# Bridge.net
KiCad netlist of a schematic drawn in Altium Designer
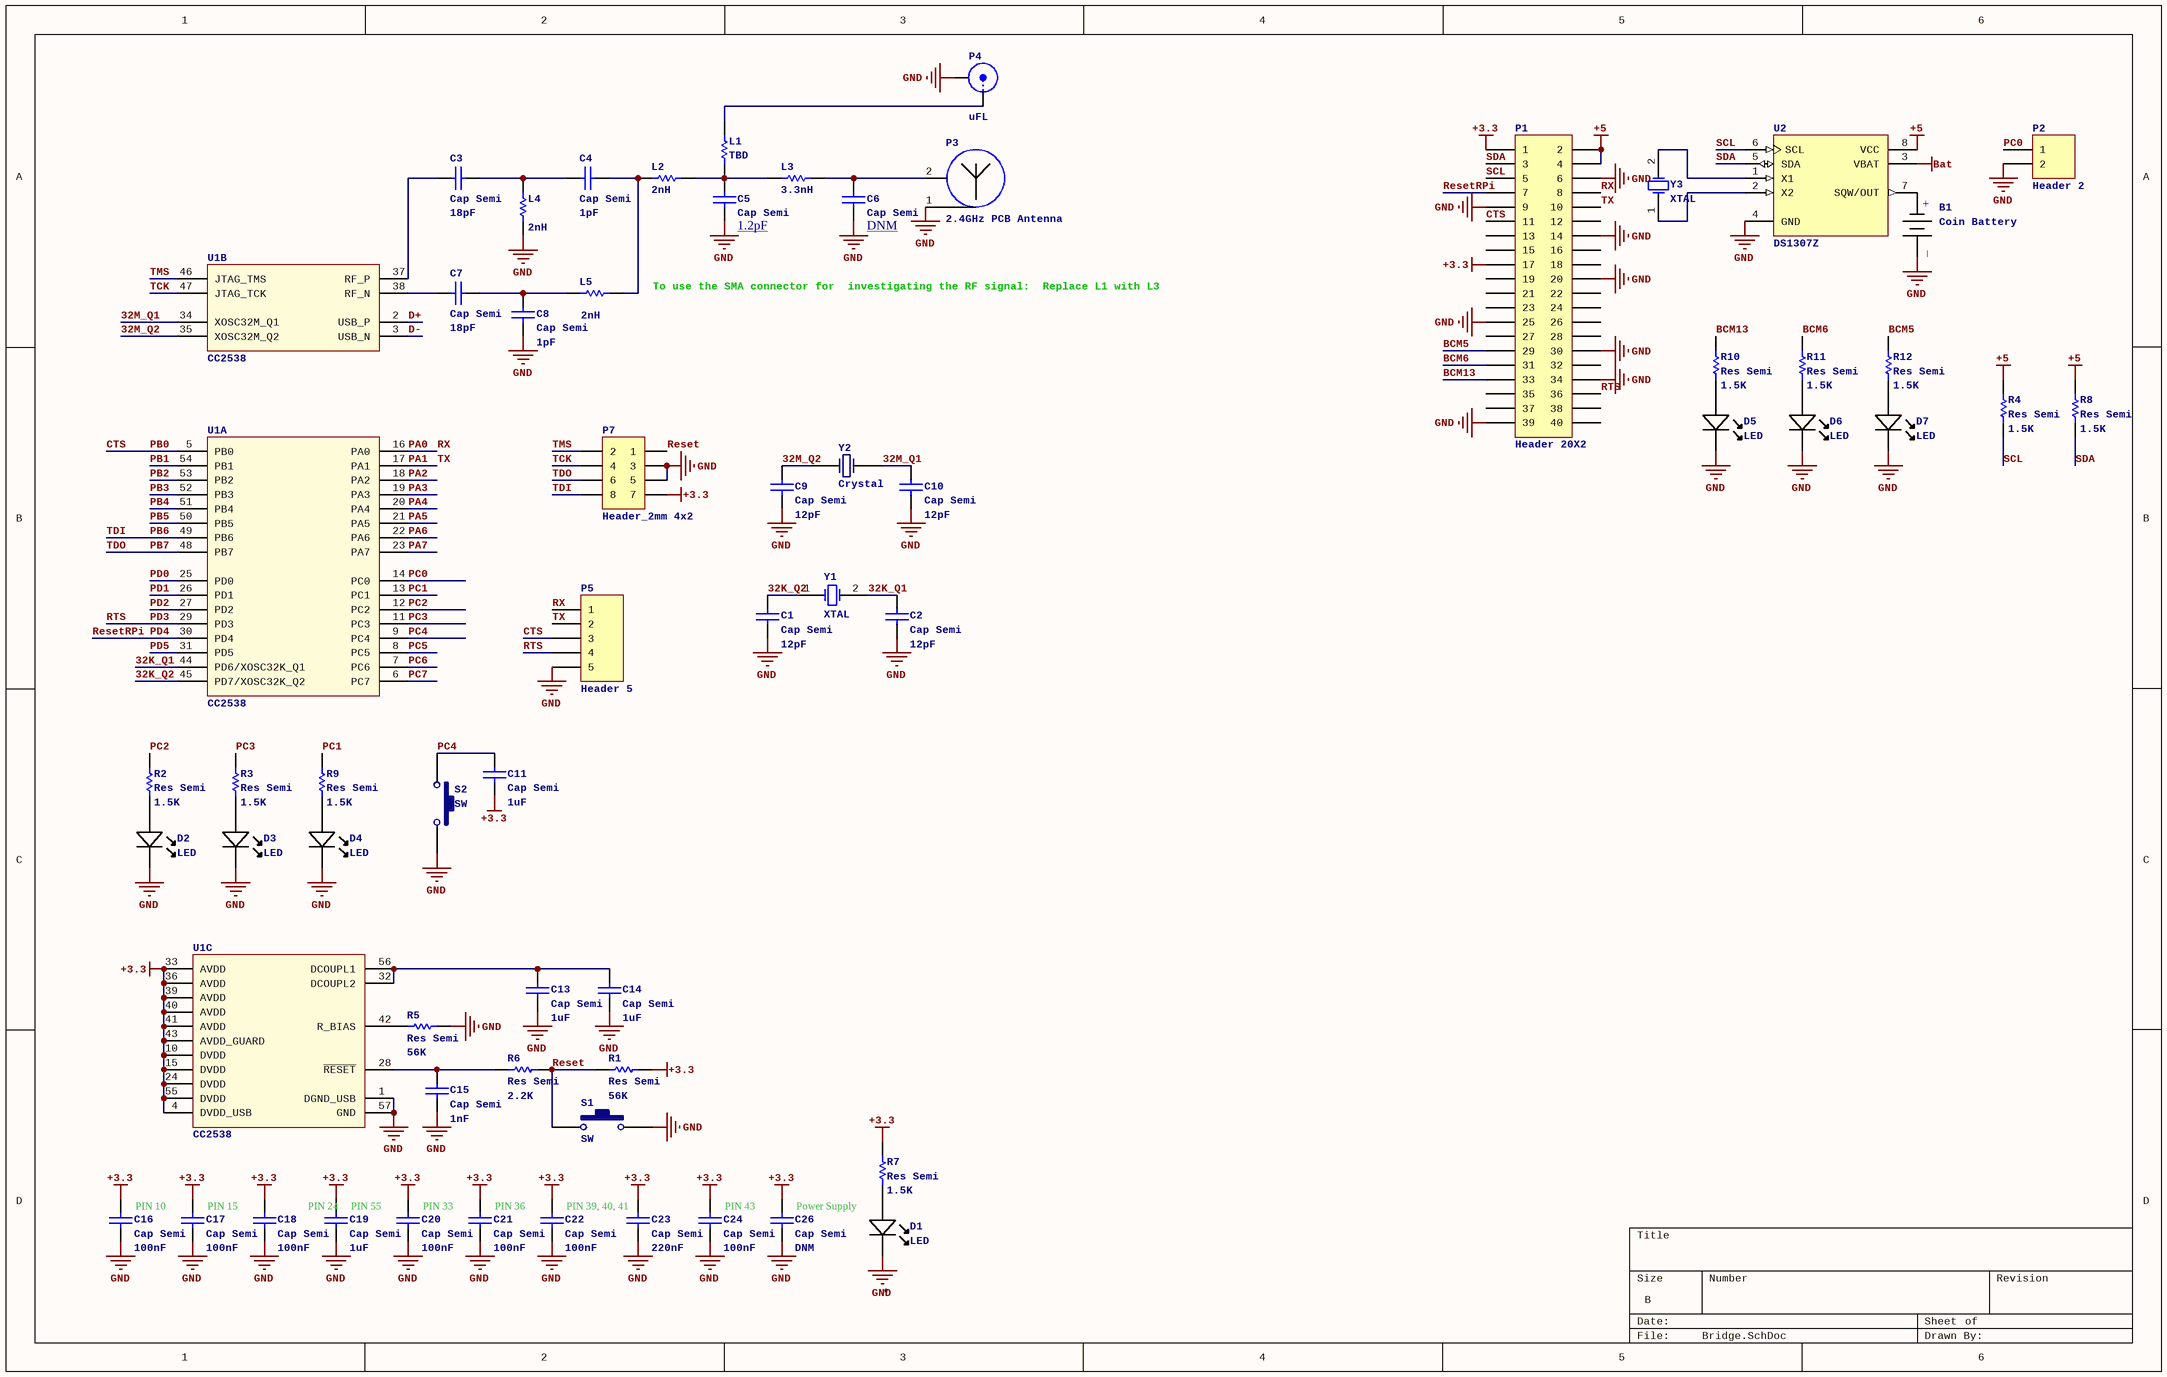
[diagram p0: Bridge.SchDoc]

(export (version "E")
  (design (tool "Eeschema 10.0.6"))
  (components
    (comp (ref "B1")
      (value "Coin Battery")
      (footprint "Coin Battery 1220")
      (libsource (lib "My Lib") (part "Coin Battery"))
    )
    (comp (ref "C1")
      (value "Cap Semi")
      (footprint "1608[0603]")
      (description "Capacitor (Semiconductor SIM Model)")
      (fields (field (name "ALTIUM_VALUE") "12pF") (field (name "PUBLISHER") "Altium Limited"))
      (libsource (lib "Miscellaneous Devices") (part "Cap Semi"))
    )
    (comp (ref "C2")
      (value "Cap Semi")
      (footprint "1608[0603]")
      (description "Capacitor (Semiconductor SIM Model)")
      (fields (field (name "ALTIUM_VALUE") "12pF") (field (name "PUBLISHER") "Altium Limited"))
      (libsource (lib "Miscellaneous Devices") (part "Cap Semi"))
    )
    (comp (ref "C3")
      (value "Cap Semi")
      (footprint "1608[0603]")
      (description "Capacitor (Semiconductor SIM Model)")
      (fields (field (name "ALTIUM_VALUE") "18pF") (field (name "PUBLISHER") "Altium Limited"))
      (libsource (lib "Miscellaneous Devices") (part "Cap Semi"))
    )
    (comp (ref "C4")
      (value "Cap Semi")
      (footprint "1608[0603]")
      (description "Capacitor (Semiconductor SIM Model)")
      (fields (field (name "ALTIUM_VALUE") "1pF") (field (name "PUBLISHER") "Altium Limited"))
      (libsource (lib "Miscellaneous Devices") (part "Cap Semi"))
    )
    (comp (ref "C5")
      (value "Cap Semi")
      (footprint "1608[0603]")
      (description "Capacitor (Semiconductor SIM Model)")
      (fields (field (name "ALTIUM_VALUE") "1.2pF") (field (name "PUBLISHER") "Altium Limited"))
      (libsource (lib "Miscellaneous Devices") (part "Cap Semi"))
    )
    (comp (ref "C6")
      (value "Cap Semi")
      (footprint "1608[0603]")
      (description "Capacitor (Semiconductor SIM Model)")
      (fields (field (name "ALTIUM_VALUE") "DNM") (field (name "PUBLISHER") "Altium Limited"))
      (libsource (lib "Miscellaneous Devices") (part "Cap Semi"))
    )
    (comp (ref "C7")
      (value "Cap Semi")
      (footprint "1608[0603]")
      (description "Capacitor (Semiconductor SIM Model)")
      (fields (field (name "ALTIUM_VALUE") "18pF") (field (name "PUBLISHER") "Altium Limited"))
      (libsource (lib "Miscellaneous Devices") (part "Cap Semi"))
    )
    (comp (ref "C8")
      (value "Cap Semi")
      (footprint "1608[0603]")
      (description "Capacitor (Semiconductor SIM Model)")
      (fields (field (name "ALTIUM_VALUE") "1pF") (field (name "PUBLISHER") "Altium Limited"))
      (libsource (lib "Miscellaneous Devices") (part "Cap Semi"))
    )
    (comp (ref "C9")
      (value "Cap Semi")
      (footprint "1608[0603]")
      (description "Capacitor (Semiconductor SIM Model)")
      (fields (field (name "ALTIUM_VALUE") "12pF") (field (name "PUBLISHER") "Altium Limited"))
      (libsource (lib "Miscellaneous Devices") (part "Cap Semi"))
    )
    (comp (ref "C10")
      (value "Cap Semi")
      (footprint "1608[0603]")
      (description "Capacitor (Semiconductor SIM Model)")
      (fields (field (name "ALTIUM_VALUE") "12pF") (field (name "PUBLISHER") "Altium Limited"))
      (libsource (lib "Miscellaneous Devices") (part "Cap Semi"))
    )
    (comp (ref "C11")
      (value "Cap Semi")
      (footprint "1608[0603]")
      (description "Capacitor (Semiconductor SIM Model)")
      (fields (field (name "ALTIUM_VALUE") "1uF") (field (name "PUBLISHER") "Altium Limited"))
      (libsource (lib "Miscellaneous Devices") (part "Cap Semi"))
    )
    (comp (ref "C13")
      (value "Cap Semi")
      (footprint "1608[0603]")
      (description "Capacitor (Semiconductor SIM Model)")
      (fields (field (name "ALTIUM_VALUE") "1uF") (field (name "PUBLISHER") "Altium Limited"))
      (libsource (lib "Miscellaneous Devices") (part "Cap Semi"))
    )
    (comp (ref "C14")
      (value "Cap Semi")
      (footprint "1608[0603]")
      (description "Capacitor (Semiconductor SIM Model)")
      (fields (field (name "ALTIUM_VALUE") "1uF") (field (name "PUBLISHER") "Altium Limited"))
      (libsource (lib "Miscellaneous Devices") (part "Cap Semi"))
    )
    (comp (ref "C15")
      (value "Cap Semi")
      (footprint "1608[0603]")
      (description "Capacitor (Semiconductor SIM Model)")
      (fields (field (name "ALTIUM_VALUE") "1nF") (field (name "PUBLISHER") "Altium Limited"))
      (libsource (lib "Miscellaneous Devices") (part "Cap Semi"))
    )
    (comp (ref "C16")
      (value "Cap Semi")
      (footprint "1608[0603]")
      (description "Capacitor (Semiconductor SIM Model)")
      (fields (field (name "ALTIUM_VALUE") "100nF") (field (name "PUBLISHER") "Altium Limited"))
      (libsource (lib "Miscellaneous Devices") (part "Cap Semi"))
    )
    (comp (ref "C17")
      (value "Cap Semi")
      (footprint "1608[0603]")
      (description "Capacitor (Semiconductor SIM Model)")
      (fields (field (name "ALTIUM_VALUE") "100nF") (field (name "PUBLISHER") "Altium Limited"))
      (libsource (lib "Miscellaneous Devices") (part "Cap Semi"))
    )
    (comp (ref "C18")
      (value "Cap Semi")
      (footprint "1608[0603]")
      (description "Capacitor (Semiconductor SIM Model)")
      (fields (field (name "ALTIUM_VALUE") "100nF") (field (name "PUBLISHER") "Altium Limited"))
      (libsource (lib "Miscellaneous Devices") (part "Cap Semi"))
    )
    (comp (ref "C19")
      (value "Cap Semi")
      (footprint "1608[0603]")
      (description "Capacitor (Semiconductor SIM Model)")
      (fields (field (name "ALTIUM_VALUE") "1uF") (field (name "PUBLISHER") "Altium Limited"))
      (libsource (lib "Miscellaneous Devices") (part "Cap Semi"))
    )
    (comp (ref "C20")
      (value "Cap Semi")
      (footprint "1608[0603]")
      (description "Capacitor (Semiconductor SIM Model)")
      (fields (field (name "ALTIUM_VALUE") "100nF") (field (name "PUBLISHER") "Altium Limited"))
      (libsource (lib "Miscellaneous Devices") (part "Cap Semi"))
    )
    (comp (ref "C21")
      (value "Cap Semi")
      (footprint "1608[0603]")
      (description "Capacitor (Semiconductor SIM Model)")
      (fields (field (name "ALTIUM_VALUE") "100nF") (field (name "PUBLISHER") "Altium Limited"))
      (libsource (lib "Miscellaneous Devices") (part "Cap Semi"))
    )
    (comp (ref "C22")
      (value "Cap Semi")
      (footprint "1608[0603]")
      (description "Capacitor (Semiconductor SIM Model)")
      (fields (field (name "ALTIUM_VALUE") "100nF") (field (name "PUBLISHER") "Altium Limited"))
      (libsource (lib "Miscellaneous Devices") (part "Cap Semi"))
    )
    (comp (ref "C23")
      (value "Cap Semi")
      (footprint "1608[0603]")
      (description "Capacitor (Semiconductor SIM Model)")
      (fields (field (name "ALTIUM_VALUE") "220nF") (field (name "PUBLISHER") "Altium Limited"))
      (libsource (lib "Miscellaneous Devices") (part "Cap Semi"))
    )
    (comp (ref "C24")
      (value "Cap Semi")
      (footprint "1608[0603]")
      (description "Capacitor (Semiconductor SIM Model)")
      (fields (field (name "ALTIUM_VALUE") "100nF") (field (name "PUBLISHER") "Altium Limited"))
      (libsource (lib "Miscellaneous Devices") (part "Cap Semi"))
    )
    (comp (ref "C26")
      (value "Cap Semi")
      (footprint "1608[0603]")
      (description "Capacitor (Semiconductor SIM Model)")
      (fields (field (name "ALTIUM_VALUE") "DNM") (field (name "PUBLISHER") "Altium Limited"))
      (libsource (lib "Miscellaneous Devices") (part "Cap Semi"))
    )
    (comp (ref "D1")
      (value "LED")
      (footprint "LED 0603")
      (description "LED SMD")
      (libsource (lib "Common") (part "LED SMD"))
    )
    (comp (ref "D2")
      (value "LED")
      (footprint "LED 0603")
      (description "LED SMD")
      (libsource (lib "Common") (part "LED SMD"))
    )
    (comp (ref "D3")
      (value "LED")
      (footprint "LED 0603")
      (description "LED SMD")
      (libsource (lib "Common") (part "LED SMD"))
    )
    (comp (ref "D4")
      (value "LED")
      (footprint "LED 0603")
      (description "LED SMD")
      (libsource (lib "Common") (part "LED SMD"))
    )
    (comp (ref "D5")
      (value "LED")
      (footprint "LED 0603")
      (description "LED SMD")
      (libsource (lib "Common") (part "LED SMD"))
    )
    (comp (ref "D6")
      (value "LED")
      (footprint "LED 0603")
      (description "LED SMD")
      (libsource (lib "Common") (part "LED SMD"))
    )
    (comp (ref "D7")
      (value "LED")
      (footprint "LED 0603")
      (description "LED SMD")
      (libsource (lib "Common") (part "LED SMD"))
    )
    (comp (ref "L1")
      (value "TBD")
      (footprint "1608[0603]")
      (description "Semiconductor Resistor")
      (fields (field (name "Comment") "Res Semi") (field (name "PUBLISHER") "Altium Limited"))
      (libsource (lib "Miscellaneous Devices") (part "Res Semi"))
    )
    (comp (ref "L2")
      (value "2nH")
      (footprint "1608[0603]")
      (description "Semiconductor Resistor")
      (fields (field (name "Comment") "Res Semi") (field (name "PUBLISHER") "Altium Limited"))
      (libsource (lib "Miscellaneous Devices") (part "Res Semi"))
    )
    (comp (ref "L3")
      (value "3.3nH")
      (footprint "1608[0603]")
      (description "Semiconductor Resistor")
      (fields (field (name "Comment") "Res Semi") (field (name "PUBLISHER") "Altium Limited"))
      (libsource (lib "Miscellaneous Devices") (part "Res Semi"))
    )
    (comp (ref "L4")
      (value "2nH")
      (footprint "1608[0603]")
      (description "Semiconductor Resistor")
      (fields (field (name "Comment") "Res Semi") (field (name "PUBLISHER") "Altium Limited"))
      (libsource (lib "Miscellaneous Devices") (part "Res Semi"))
    )
    (comp (ref "L5")
      (value "2nH")
      (footprint "1608[0603]")
      (description "Semiconductor Resistor")
      (fields (field (name "Comment") "Res Semi") (field (name "PUBLISHER") "Altium Limited"))
      (libsource (lib "Miscellaneous Devices") (part "Res Semi"))
    )
    (comp (ref "P1")
      (value "Header 20X2")
      (footprint "HDR2X20")
      (description "Header, 20-Pin, Dual row")
      (fields (field (name "PUBLISHER") "Altium Limited"))
      (libsource (lib "Miscellaneous Connectors") (part "Header 20X2"))
    )
    (comp (ref "P2")
      (value "Header 2")
      (footprint "HDR1X2")
      (description "Header, 2-Pin")
      (fields (field (name "PUBLISHER") "Altium Limited"))
      (libsource (lib "Miscellaneous Connectors") (part "Header 2"))
    )
    (comp (ref "P3")
      (value "2.4GHz PCB Antenna")
      (footprint "2.4 GHz Inverted F Antenna 1")
      (libsource (lib "My Lib") (part "2.4GHz PCB Antenna"))
    )
    (comp (ref "P4") (value "uFL") (footprint "uFL") (libsource (lib "Common") (part "uFL")))
    (comp (ref "P5")
      (value "Header 5")
      (footprint "HDR1X5")
      (description "Header, 5-Pin")
      (fields (field (name "PUBLISHER") "Altium Limited"))
      (libsource (lib "Miscellaneous Connectors") (part "Header 5"))
    )
    (comp (ref "P7")
      (value "Header_2mm 4x2")
      (footprint "Header_2mm 4x2")
      (libsource (lib "Common") (part "Header_2mm 4x2"))
    )
    (comp (ref "R1")
      (value "Res Semi")
      (footprint "1608[0603]")
      (description "Semiconductor Resistor")
      (fields (field (name "ALTIUM_VALUE") "56K") (field (name "PUBLISHER") "Altium Limited"))
      (libsource (lib "Miscellaneous Devices") (part "Res Semi"))
    )
    (comp (ref "R2")
      (value "Res Semi")
      (footprint "1608[0603]")
      (description "Semiconductor Resistor")
      (fields (field (name "ALTIUM_VALUE") "1.5K") (field (name "PUBLISHER") "Altium Limited"))
      (libsource (lib "Miscellaneous Devices") (part "Res Semi"))
    )
    (comp (ref "R3")
      (value "Res Semi")
      (footprint "1608[0603]")
      (description "Semiconductor Resistor")
      (fields (field (name "ALTIUM_VALUE") "1.5K") (field (name "PUBLISHER") "Altium Limited"))
      (libsource (lib "Miscellaneous Devices") (part "Res Semi"))
    )
    (comp (ref "R4")
      (value "Res Semi")
      (footprint "1608[0603]")
      (description "Semiconductor Resistor")
      (fields (field (name "ALTIUM_VALUE") "1.5K") (field (name "PUBLISHER") "Altium Limited"))
      (libsource (lib "Miscellaneous Devices") (part "Res Semi"))
    )
    (comp (ref "R5")
      (value "Res Semi")
      (footprint "1608[0603]")
      (description "Semiconductor Resistor")
      (fields (field (name "ALTIUM_VALUE") "56K") (field (name "PUBLISHER") "Altium Limited"))
      (libsource (lib "Miscellaneous Devices") (part "Res Semi"))
    )
    (comp (ref "R6")
      (value "Res Semi")
      (footprint "1608[0603]")
      (description "Semiconductor Resistor")
      (fields (field (name "ALTIUM_VALUE") "2.2K") (field (name "PUBLISHER") "Altium Limited"))
      (libsource (lib "Miscellaneous Devices") (part "Res Semi"))
    )
    (comp (ref "R7")
      (value "Res Semi")
      (footprint "1608[0603]")
      (description "Semiconductor Resistor")
      (fields (field (name "ALTIUM_VALUE") "1.5K") (field (name "PUBLISHER") "Altium Limited"))
      (libsource (lib "Miscellaneous Devices") (part "Res Semi"))
    )
    (comp (ref "R8")
      (value "Res Semi")
      (footprint "1608[0603]")
      (description "Semiconductor Resistor")
      (fields (field (name "ALTIUM_VALUE") "1.5K") (field (name "PUBLISHER") "Altium Limited"))
      (libsource (lib "Miscellaneous Devices") (part "Res Semi"))
    )
    (comp (ref "R9")
      (value "Res Semi")
      (footprint "1608[0603]")
      (description "Semiconductor Resistor")
      (fields (field (name "ALTIUM_VALUE") "1.5K") (field (name "PUBLISHER") "Altium Limited"))
      (libsource (lib "Miscellaneous Devices") (part "Res Semi"))
    )
    (comp (ref "R10")
      (value "Res Semi")
      (footprint "1608[0603]")
      (description "Semiconductor Resistor")
      (fields (field (name "ALTIUM_VALUE") "1.5K") (field (name "PUBLISHER") "Altium Limited"))
      (libsource (lib "Miscellaneous Devices") (part "Res Semi"))
    )
    (comp (ref "R11")
      (value "Res Semi")
      (footprint "1608[0603]")
      (description "Semiconductor Resistor")
      (fields (field (name "ALTIUM_VALUE") "1.5K") (field (name "PUBLISHER") "Altium Limited"))
      (libsource (lib "Miscellaneous Devices") (part "Res Semi"))
    )
    (comp (ref "R12")
      (value "Res Semi")
      (footprint "1608[0603]")
      (description "Semiconductor Resistor")
      (fields (field (name "ALTIUM_VALUE") "1.5K") (field (name "PUBLISHER") "Altium Limited"))
      (libsource (lib "Miscellaneous Devices") (part "Res Semi"))
    )
    (comp (ref "S1") (value "SW") (footprint "Switch SMD") (libsource (lib "My Lib") (part "Switch SMD")))
    (comp (ref "S2") (value "SW") (footprint "Switch SMD") (libsource (lib "My Lib") (part "Switch SMD")))
    (comp (ref "U1") (value "CC2538") (footprint "PVQFN56-CC2538") (libsource (lib "My Lib") (part "CC2538")))
    (comp (ref "U2")
      (value "DS1307Z")
      (footprint "SOIC8N_N")
      (description "64 X 8 Serial Real-Time Clock")
      (fields (field (name "PUBLISHER") "Altium Limited"))
      (libsource (lib "Dallas Peripheral Real Time Clock") (part "DS1307Z"))
    )
    (comp (ref "Y1")
      (value "XTAL")
      (footprint "R38")
      (description "Crystal Oscillator")
      (fields (field (name "PUBLISHER") "Altium Limited"))
      (libsource (lib "Miscellaneous Devices") (part "XTAL"))
    )
    (comp (ref "Y2") (value "Crystal") (footprint "Crystal 3225") (libsource (lib "Common") (part "Xtal")))
    (comp (ref "Y3")
      (value "XTAL")
      (footprint "R38")
      (description "Crystal Oscillator")
      (fields (field (name "PUBLISHER") "Altium Limited"))
      (libsource (lib "Miscellaneous Devices") (part "XTAL"))
    )
  )
  (nets
    (net (code "1") (name "+3.3") (class "Default")
      (node (ref "C11") (pin "1") (pinfunction "1_1") (pintype "passive"))
      (node (ref "C16") (pin "2") (pinfunction "2_2") (pintype "passive"))
      (node (ref "C17") (pin "2") (pinfunction "2_2") (pintype "passive"))
      (node (ref "C18") (pin "2") (pinfunction "2_2") (pintype "passive"))
      (node (ref "C19") (pin "2") (pinfunction "2_2") (pintype "passive"))
      (node (ref "C20") (pin "2") (pinfunction "2_2") (pintype "passive"))
      (node (ref "C21") (pin "2") (pinfunction "2_2") (pintype "passive"))
      (node (ref "C22") (pin "2") (pinfunction "2_2") (pintype "passive"))
      (node (ref "C23") (pin "2") (pinfunction "2_2") (pintype "passive"))
      (node (ref "C24") (pin "2") (pinfunction "2_2") (pintype "passive"))
      (node (ref "C26") (pin "2") (pinfunction "2_2") (pintype "passive"))
      (node (ref "P1") (pin "1") (pinfunction "1_1") (pintype "passive"))
      (node (ref "P1") (pin "17") (pinfunction "17_17") (pintype "passive"))
      (node (ref "P7") (pin "7") (pinfunction "7_7") (pintype "passive"))
      (node (ref "R1") (pin "1") (pinfunction "1_1") (pintype "passive"))
      (node (ref "R7") (pin "2") (pinfunction "2_2") (pintype "passive"))
      (node (ref "U1") (pin "10") (pinfunction "DVDD_10") (pintype "power_in"))
      (node (ref "U1") (pin "15") (pinfunction "DVDD_15") (pintype "power_in"))
      (node (ref "U1") (pin "24") (pinfunction "DVDD_24") (pintype "power_in"))
      (node (ref "U1") (pin "33") (pinfunction "AVDD_33") (pintype "power_in"))
      (node (ref "U1") (pin "36") (pinfunction "AVDD_36") (pintype "power_in"))
      (node (ref "U1") (pin "39") (pinfunction "AVDD_39") (pintype "power_in"))
      (node (ref "U1") (pin "4") (pinfunction "DVDD_USB_4") (pintype "power_in"))
      (node (ref "U1") (pin "40") (pinfunction "AVDD_40") (pintype "power_in"))
      (node (ref "U1") (pin "41") (pinfunction "AVDD_41") (pintype "power_in"))
      (node (ref "U1") (pin "43") (pinfunction "AVDD_GUARD_43") (pintype "power_in"))
      (node (ref "U1") (pin "55") (pinfunction "DVDD_55") (pintype "power_in"))
    )
    (net (code "2") (name "+5") (class "Default")
      (node (ref "P1") (pin "2") (pinfunction "2_2") (pintype "passive"))
      (node (ref "P1") (pin "4") (pinfunction "4_4") (pintype "passive"))
      (node (ref "R4") (pin "2") (pinfunction "2_2") (pintype "passive"))
      (node (ref "R8") (pin "2") (pinfunction "2_2") (pintype "passive"))
      (node (ref "U2") (pin "8") (pinfunction "VCC_8") (pintype "power_in"))
    )
    (net (code "3") (name "/32K_Q1") (class "Default")
      (node (ref "C2") (pin "2") (pinfunction "2_2") (pintype "passive"))
      (node (ref "U1") (pin "44") (pinfunction "PD6/XOSC32K_Q1_44") (pintype "power_in"))
      (node (ref "Y1") (pin "2") (pinfunction "OSC2_2") (pintype "passive"))
    )
    (net (code "4") (name "/32K_Q2") (class "Default")
      (node (ref "C1") (pin "2") (pinfunction "2_2") (pintype "passive"))
      (node (ref "U1") (pin "45") (pinfunction "PD7/XOSC32K_Q2_45") (pintype "power_in"))
      (node (ref "Y1") (pin "1") (pinfunction "OSC1_1") (pintype "passive"))
    )
    (net (code "5") (name "/32M_Q1") (class "Default")
      (node (ref "C10") (pin "2") (pinfunction "2_2") (pintype "passive"))
      (node (ref "U1") (pin "34") (pinfunction "XOSC32M_Q1_34") (pintype "passive"))
      (node (ref "Y2") (pin "2") (pinfunction "2_2") (pintype "passive"))
    )
    (net (code "6") (name "/32M_Q2") (class "Default")
      (node (ref "C9") (pin "2") (pinfunction "2_2") (pintype "passive"))
      (node (ref "U1") (pin "35") (pinfunction "XOSC32M_Q2_35") (pintype "passive"))
      (node (ref "Y2") (pin "1") (pinfunction "1_1") (pintype "passive"))
    )
    (net (code "7") (name "/BCM5") (class "Default")
      (node (ref "P1") (pin "29") (pinfunction "29_29") (pintype "passive"))
      (node (ref "R12") (pin "2") (pinfunction "2_2") (pintype "passive"))
    )
    (net (code "8") (name "/BCM6") (class "Default")
      (node (ref "P1") (pin "31") (pinfunction "31_31") (pintype "passive"))
      (node (ref "R11") (pin "2") (pinfunction "2_2") (pintype "passive"))
    )
    (net (code "9") (name "/BCM13") (class "Default")
      (node (ref "P1") (pin "33") (pinfunction "33_33") (pintype "passive"))
      (node (ref "R10") (pin "2") (pinfunction "2_2") (pintype "passive"))
    )
    (net (code "10") (name "/CTS") (class "Default")
      (node (ref "P1") (pin "11") (pinfunction "11_11") (pintype "passive"))
      (node (ref "P5") (pin "3") (pinfunction "3_3") (pintype "passive"))
      (node (ref "U1") (pin "5") (pinfunction "PB0_5") (pintype "power_in"))
    )
    (net (code "11") (name "/D+") (class "Default")
      (node (ref "U1") (pin "2") (pinfunction "USB_P_2") (pintype "passive"))
    )
    (net (code "12") (name "/D-") (class "Default")
      (node (ref "U1") (pin "3") (pinfunction "USB_N_3") (pintype "passive"))
    )
    (net (code "13") (name "/PA0") (class "Default")
      (node (ref "P1") (pin "8") (pinfunction "8_8") (pintype "passive"))
      (node (ref "P5") (pin "1") (pinfunction "1_1") (pintype "passive"))
      (node (ref "U1") (pin "16") (pinfunction "PA0_16") (pintype "power_in"))
    )
    (net (code "14") (name "/PA1") (class "Default")
      (node (ref "P1") (pin "10") (pinfunction "10_10") (pintype "passive"))
      (node (ref "P5") (pin "2") (pinfunction "2_2") (pintype "passive"))
      (node (ref "U1") (pin "17") (pinfunction "PA1_17") (pintype "power_in"))
    )
    (net (code "15") (name "/PA2") (class "Default")
      (node (ref "U1") (pin "18") (pinfunction "PA2_18") (pintype "power_in"))
    )
    (net (code "16") (name "/PA3") (class "Default")
      (node (ref "U1") (pin "19") (pinfunction "PA3_19") (pintype "power_in"))
    )
    (net (code "17") (name "/PA4") (class "Default")
      (node (ref "U1") (pin "20") (pinfunction "PA4_20") (pintype "power_in"))
    )
    (net (code "18") (name "/PA5") (class "Default")
      (node (ref "U1") (pin "21") (pinfunction "PA5_21") (pintype "power_in"))
    )
    (net (code "19") (name "/PA6") (class "Default")
      (node (ref "U1") (pin "22") (pinfunction "PA6_22") (pintype "power_in"))
    )
    (net (code "20") (name "/PA7") (class "Default")
      (node (ref "U1") (pin "23") (pinfunction "PA7_23") (pintype "power_in"))
    )
    (net (code "21") (name "/PB1") (class "Default")
      (node (ref "U1") (pin "54") (pinfunction "PB1_54") (pintype "power_in"))
    )
    (net (code "22") (name "/PB2") (class "Default")
      (node (ref "U1") (pin "53") (pinfunction "PB2_53") (pintype "power_in"))
    )
    (net (code "23") (name "/PB3") (class "Default")
      (node (ref "U1") (pin "52") (pinfunction "PB3_52") (pintype "power_in"))
    )
    (net (code "24") (name "/PB4") (class "Default")
      (node (ref "U1") (pin "51") (pinfunction "PB4_51") (pintype "power_in"))
    )
    (net (code "25") (name "/PB5") (class "Default")
      (node (ref "U1") (pin "50") (pinfunction "PB5_50") (pintype "power_in"))
    )
    (net (code "26") (name "/PB6") (class "Default")
      (node (ref "P7") (pin "8") (pinfunction "8_8") (pintype "passive"))
      (node (ref "U1") (pin "49") (pinfunction "PB6_49") (pintype "power_in"))
    )
    (net (code "27") (name "/PB7") (class "Default")
      (node (ref "P7") (pin "6") (pinfunction "6_6") (pintype "passive"))
      (node (ref "U1") (pin "48") (pinfunction "PB7_48") (pintype "power_in"))
    )
    (net (code "28") (name "/PC0") (class "Default")
      (node (ref "P2") (pin "1") (pinfunction "1_1") (pintype "passive"))
      (node (ref "U1") (pin "14") (pinfunction "PC0_14") (pintype "power_in"))
    )
    (net (code "29") (name "/PC1") (class "Default")
      (node (ref "R9") (pin "2") (pinfunction "2_2") (pintype "passive"))
      (node (ref "U1") (pin "13") (pinfunction "PC1_13") (pintype "power_in"))
    )
    (net (code "30") (name "/PC2") (class "Default")
      (node (ref "R2") (pin "2") (pinfunction "2_2") (pintype "passive"))
      (node (ref "U1") (pin "12") (pinfunction "PC2_12") (pintype "power_in"))
    )
    (net (code "31") (name "/PC3") (class "Default")
      (node (ref "R3") (pin "2") (pinfunction "2_2") (pintype "passive"))
      (node (ref "U1") (pin "11") (pinfunction "PC3_11") (pintype "power_in"))
    )
    (net (code "32") (name "/PC4") (class "Default")
      (node (ref "C11") (pin "2") (pinfunction "2_2") (pintype "passive"))
      (node (ref "S2") (pin "2") (pinfunction "2_2") (pintype "passive"))
      (node (ref "U1") (pin "9") (pinfunction "PC4_9") (pintype "power_in"))
    )
    (net (code "33") (name "/PC5") (class "Default")
      (node (ref "U1") (pin "8") (pinfunction "PC5_8") (pintype "power_in"))
    )
    (net (code "34") (name "/PC6") (class "Default")
      (node (ref "U1") (pin "7") (pinfunction "PC6_7") (pintype "power_in"))
    )
    (net (code "35") (name "/PC7") (class "Default")
      (node (ref "U1") (pin "6") (pinfunction "PC7_6") (pintype "power_in"))
    )
    (net (code "36") (name "/PD0") (class "Default")
      (node (ref "U1") (pin "25") (pinfunction "PD0_25") (pintype "power_in"))
    )
    (net (code "37") (name "/PD1") (class "Default")
      (node (ref "U1") (pin "26") (pinfunction "PD1_26") (pintype "power_in"))
    )
    (net (code "38") (name "/PD2") (class "Default")
      (node (ref "U1") (pin "27") (pinfunction "PD2_27") (pintype "power_in"))
    )
    (net (code "39") (name "/PD3") (class "Default")
      (node (ref "P1") (pin "36") (pinfunction "36_36") (pintype "passive"))
      (node (ref "P5") (pin "4") (pinfunction "4_4") (pintype "passive"))
      (node (ref "U1") (pin "29") (pinfunction "PD3_29") (pintype "power_in"))
    )
    (net (code "40") (name "/PD4") (class "Default")
      (node (ref "P1") (pin "7") (pinfunction "7_7") (pintype "passive"))
      (node (ref "U1") (pin "30") (pinfunction "PD4_30") (pintype "power_in"))
    )
    (net (code "41") (name "/PD5") (class "Default")
      (node (ref "U1") (pin "31") (pinfunction "PD5_31") (pintype "power_in"))
    )
    (net (code "42") (name "/Reset") (class "Default")
      (node (ref "P7") (pin "1") (pinfunction "1_1") (pintype "passive"))
      (node (ref "R1") (pin "2") (pinfunction "2_2") (pintype "passive"))
      (node (ref "R6") (pin "1") (pinfunction "1_1") (pintype "passive"))
      (node (ref "S1") (pin "2") (pinfunction "2_2") (pintype "passive"))
    )
    (net (code "43") (name "/SCL") (class "Default")
      (node (ref "P1") (pin "5") (pinfunction "5_5") (pintype "passive"))
      (node (ref "R4") (pin "1") (pinfunction "1_1") (pintype "passive"))
      (node (ref "U2") (pin "6") (pinfunction "SCL_6") (pintype "input"))
    )
    (net (code "44") (name "/SDA") (class "Default")
      (node (ref "P1") (pin "3") (pinfunction "3_3") (pintype "passive"))
      (node (ref "R8") (pin "1") (pinfunction "1_1") (pintype "passive"))
      (node (ref "U2") (pin "5") (pinfunction "SDA_5") (pintype "bidirectional"))
    )
    (net (code "45") (name "/TCK") (class "Default")
      (node (ref "P7") (pin "4") (pinfunction "4_4") (pintype "passive"))
      (node (ref "U1") (pin "47") (pinfunction "JTAG_TCK_47") (pintype "power_in"))
    )
    (net (code "46") (name "/TMS") (class "Default")
      (node (ref "P7") (pin "2") (pinfunction "2_2") (pintype "passive"))
      (node (ref "U1") (pin "46") (pinfunction "JTAG_TMS_46") (pintype "power_in"))
    )
    (net (code "47") (name "Bat") (class "Default")
      (node (ref "U2") (pin "3") (pinfunction "VBAT_3") (pintype "power_in"))
    )
    (net (code "48") (name "GND") (class "Default")
      (node (ref "B1") (pin "1") (pinfunction "1_1") (pintype "passive"))
      (node (ref "C1") (pin "1") (pinfunction "1_1") (pintype "passive"))
      (node (ref "C10") (pin "1") (pinfunction "1_1") (pintype "passive"))
      (node (ref "C13") (pin "1") (pinfunction "1_1") (pintype "passive"))
      (node (ref "C14") (pin "1") (pinfunction "1_1") (pintype "passive"))
      (node (ref "C15") (pin "1") (pinfunction "1_1") (pintype "passive"))
      (node (ref "C16") (pin "1") (pinfunction "1_1") (pintype "passive"))
      (node (ref "C17") (pin "1") (pinfunction "1_1") (pintype "passive"))
      (node (ref "C18") (pin "1") (pinfunction "1_1") (pintype "passive"))
      (node (ref "C19") (pin "1") (pinfunction "1_1") (pintype "passive"))
      (node (ref "C2") (pin "1") (pinfunction "1_1") (pintype "passive"))
      (node (ref "C20") (pin "1") (pinfunction "1_1") (pintype "passive"))
      (node (ref "C21") (pin "1") (pinfunction "1_1") (pintype "passive"))
      (node (ref "C22") (pin "1") (pinfunction "1_1") (pintype "passive"))
      (node (ref "C23") (pin "1") (pinfunction "1_1") (pintype "passive"))
      (node (ref "C24") (pin "1") (pinfunction "1_1") (pintype "passive"))
      (node (ref "C26") (pin "1") (pinfunction "1_1") (pintype "passive"))
      (node (ref "C5") (pin "1") (pinfunction "1_1") (pintype "passive"))
      (node (ref "C6") (pin "1") (pinfunction "1_1") (pintype "passive"))
      (node (ref "C8") (pin "1") (pinfunction "1_1") (pintype "passive"))
      (node (ref "C9") (pin "1") (pinfunction "1_1") (pintype "passive"))
      (node (ref "D1") (pin "K") (pinfunction "K_K") (pintype "passive"))
      (node (ref "D2") (pin "K") (pinfunction "K_K") (pintype "passive"))
      (node (ref "D3") (pin "K") (pinfunction "K_K") (pintype "passive"))
      (node (ref "D4") (pin "K") (pinfunction "K_K") (pintype "passive"))
      (node (ref "D5") (pin "K") (pinfunction "K_K") (pintype "passive"))
      (node (ref "D6") (pin "K") (pinfunction "K_K") (pintype "passive"))
      (node (ref "D7") (pin "K") (pinfunction "K_K") (pintype "passive"))
      (node (ref "L4") (pin "1") (pinfunction "1_1") (pintype "passive"))
      (node (ref "P1") (pin "14") (pinfunction "14_14") (pintype "passive"))
      (node (ref "P1") (pin "20") (pinfunction "20_20") (pintype "passive"))
      (node (ref "P1") (pin "25") (pinfunction "25_25") (pintype "passive"))
      (node (ref "P1") (pin "30") (pinfunction "30_30") (pintype "passive"))
      (node (ref "P1") (pin "34") (pinfunction "34_34") (pintype "passive"))
      (node (ref "P1") (pin "39") (pinfunction "39_39") (pintype "passive"))
      (node (ref "P1") (pin "6") (pinfunction "6_6") (pintype "passive"))
      (node (ref "P1") (pin "9") (pinfunction "9_9") (pintype "passive"))
      (node (ref "P2") (pin "2") (pinfunction "2_2") (pintype "passive"))
      (node (ref "P3") (pin "1") (pintype "passive"))
      (node (ref "P4") (pin "2") (pinfunction "2_2") (pintype "passive"))
      (node (ref "P5") (pin "5") (pinfunction "5_5") (pintype "passive"))
      (node (ref "P7") (pin "3") (pinfunction "3_3") (pintype "passive"))
      (node (ref "P7") (pin "5") (pinfunction "5_5") (pintype "passive"))
      (node (ref "R5") (pin "1") (pinfunction "1_1") (pintype "passive"))
      (node (ref "S1") (pin "1") (pinfunction "1_1") (pintype "passive"))
      (node (ref "S2") (pin "1") (pinfunction "1_1") (pintype "passive"))
      (node (ref "U1") (pin "1") (pinfunction "DGND_USB_1") (pintype "power_in"))
      (node (ref "U1") (pin "57") (pinfunction "GND_57") (pintype "power_in"))
      (node (ref "U2") (pin "4") (pinfunction "GND_4") (pintype "power_in"))
    )
    (net (code "49") (name "Net-(C3-Pad2)") (class "Default")
      (node (ref "C3") (pin "2") (pinfunction "2_2") (pintype "passive"))
      (node (ref "C4") (pin "1") (pinfunction "1_1") (pintype "passive"))
      (node (ref "L4") (pin "2") (pinfunction "2_2") (pintype "passive"))
    )
    (net (code "50") (name "Net-(C4-Pad2)") (class "Default")
      (node (ref "C4") (pin "2") (pinfunction "2_2") (pintype "passive"))
      (node (ref "L2") (pin "2") (pinfunction "2_2") (pintype "passive"))
      (node (ref "L5") (pin "2") (pinfunction "2_2") (pintype "passive"))
    )
    (net (code "51") (name "Net-(C5-Pad2)") (class "Default")
      (node (ref "C5") (pin "2") (pinfunction "2_2") (pintype "passive"))
      (node (ref "L1") (pin "2") (pinfunction "2_2") (pintype "passive"))
      (node (ref "L2") (pin "1") (pinfunction "1_1") (pintype "passive"))
      (node (ref "L3") (pin "2") (pinfunction "2_2") (pintype "passive"))
    )
    (net (code "52") (name "Net-(C6-Pad2)") (class "Default")
      (node (ref "C6") (pin "2") (pinfunction "2_2") (pintype "passive"))
      (node (ref "L3") (pin "1") (pinfunction "1_1") (pintype "passive"))
      (node (ref "P3") (pin "2") (pintype "passive"))
    )
    (net (code "53") (name "Net-(C7-Pad2)") (class "Default")
      (node (ref "C7") (pin "2") (pinfunction "2_2") (pintype "passive"))
      (node (ref "C8") (pin "2") (pinfunction "2_2") (pintype "passive"))
      (node (ref "L5") (pin "1") (pinfunction "1_1") (pintype "passive"))
    )
    (net (code "54") (name "Net-(D1-PadA)") (class "Default")
      (node (ref "D1") (pin "A") (pinfunction "A_A") (pintype "passive"))
      (node (ref "R7") (pin "1") (pinfunction "1_1") (pintype "passive"))
    )
    (net (code "55") (name "Net-(D2-PadA)") (class "Default")
      (node (ref "D2") (pin "A") (pinfunction "A_A") (pintype "passive"))
      (node (ref "R2") (pin "1") (pinfunction "1_1") (pintype "passive"))
    )
    (net (code "56") (name "Net-(D3-PadA)") (class "Default")
      (node (ref "D3") (pin "A") (pinfunction "A_A") (pintype "passive"))
      (node (ref "R3") (pin "1") (pinfunction "1_1") (pintype "passive"))
    )
    (net (code "57") (name "Net-(D4-PadA)") (class "Default")
      (node (ref "D4") (pin "A") (pinfunction "A_A") (pintype "passive"))
      (node (ref "R9") (pin "1") (pinfunction "1_1") (pintype "passive"))
    )
    (net (code "58") (name "Net-(D5-PadA)") (class "Default")
      (node (ref "D5") (pin "A") (pinfunction "A_A") (pintype "passive"))
      (node (ref "R10") (pin "1") (pinfunction "1_1") (pintype "passive"))
    )
    (net (code "59") (name "Net-(D6-PadA)") (class "Default")
      (node (ref "D6") (pin "A") (pinfunction "A_A") (pintype "passive"))
      (node (ref "R11") (pin "1") (pinfunction "1_1") (pintype "passive"))
    )
    (net (code "60") (name "Net-(D7-PadA)") (class "Default")
      (node (ref "D7") (pin "A") (pinfunction "A_A") (pintype "passive"))
      (node (ref "R12") (pin "1") (pinfunction "1_1") (pintype "passive"))
    )
    (net (code "61") (name "Net-(L1-Pad1)") (class "Default")
      (node (ref "L1") (pin "1") (pinfunction "1_1") (pintype "passive"))
      (node (ref "P4") (pin "1") (pinfunction "1_1") (pintype "passive"))
    )
    (net (code "62") (name "Net-(U1B-RF_N)") (class "Default")
      (node (ref "C7") (pin "1") (pinfunction "1_1") (pintype "passive"))
      (node (ref "U1") (pin "38") (pinfunction "RF_N_38") (pintype "passive"))
    )
    (net (code "63") (name "Net-(U1B-RF_P)") (class "Default")
      (node (ref "C3") (pin "1") (pinfunction "1_1") (pintype "passive"))
      (node (ref "U1") (pin "37") (pinfunction "RF_P_37") (pintype "passive"))
    )
    (net (code "64") (name "Net-(U1C-DCOUPL1)") (class "Default")
      (node (ref "C13") (pin "2") (pinfunction "2_2") (pintype "passive"))
      (node (ref "C14") (pin "2") (pinfunction "2_2") (pintype "passive"))
      (node (ref "U1") (pin "32") (pinfunction "DCOUPL2_32") (pintype "power_in"))
      (node (ref "U1") (pin "56") (pinfunction "DCOUPL1_56") (pintype "power_in"))
    )
    (net (code "65") (name "Net-(U1C-R_BIAS)") (class "Default")
      (node (ref "R5") (pin "2") (pinfunction "2_2") (pintype "passive"))
      (node (ref "U1") (pin "42") (pinfunction "R_BIAS_42") (pintype "passive"))
    )
    (net (code "66") (name "Net-(U1C-~{RESET})") (class "Default")
      (node (ref "C15") (pin "2") (pinfunction "2_2") (pintype "passive"))
      (node (ref "R6") (pin "2") (pinfunction "2_2") (pintype "passive"))
      (node (ref "U1") (pin "28") (pinfunction "~{RESET}_28") (pintype "power_in"))
    )
    (net (code "67") (name "Net-(U2-SQW{slash}OUT)") (class "Default")
      (node (ref "B1") (pin "2") (pinfunction "2_2") (pintype "passive"))
      (node (ref "U2") (pin "7") (pinfunction "SQW/OUT_7") (pintype "output"))
    )
    (net (code "68") (name "Net-(U2-X1)") (class "Default")
      (node (ref "U2") (pin "1") (pinfunction "X1_1") (pintype "input"))
      (node (ref "Y3") (pin "2") (pinfunction "OSC2_2") (pintype "passive"))
    )
    (net (code "69") (name "Net-(U2-X2)") (class "Default")
      (node (ref "U2") (pin "2") (pinfunction "X2_2") (pintype "input"))
      (node (ref "Y3") (pin "1") (pinfunction "OSC1_1") (pintype "passive"))
    )
    (net (code "70") (name "unconnected-(P1-Pad12)") (class "Default")
      (node (ref "P1") (pin "12") (pinfunction "12_12") (pintype "passive"))
    )
    (net (code "71") (name "unconnected-(P1-Pad13)") (class "Default")
      (node (ref "P1") (pin "13") (pinfunction "13_13") (pintype "passive"))
    )
    (net (code "72") (name "unconnected-(P1-Pad15)") (class "Default")
      (node (ref "P1") (pin "15") (pinfunction "15_15") (pintype "passive"))
    )
    (net (code "73") (name "unconnected-(P1-Pad16)") (class "Default")
      (node (ref "P1") (pin "16") (pinfunction "16_16") (pintype "passive"))
    )
    (net (code "74") (name "unconnected-(P1-Pad18)") (class "Default")
      (node (ref "P1") (pin "18") (pinfunction "18_18") (pintype "passive"))
    )
    (net (code "75") (name "unconnected-(P1-Pad19)") (class "Default")
      (node (ref "P1") (pin "19") (pinfunction "19_19") (pintype "passive"))
    )
    (net (code "76") (name "unconnected-(P1-Pad21)") (class "Default")
      (node (ref "P1") (pin "21") (pinfunction "21_21") (pintype "passive"))
    )
    (net (code "77") (name "unconnected-(P1-Pad22)") (class "Default")
      (node (ref "P1") (pin "22") (pinfunction "22_22") (pintype "passive"))
    )
    (net (code "78") (name "unconnected-(P1-Pad23)") (class "Default")
      (node (ref "P1") (pin "23") (pinfunction "23_23") (pintype "passive"))
    )
    (net (code "79") (name "unconnected-(P1-Pad24)") (class "Default")
      (node (ref "P1") (pin "24") (pinfunction "24_24") (pintype "passive"))
    )
    (net (code "80") (name "unconnected-(P1-Pad26)") (class "Default")
      (node (ref "P1") (pin "26") (pinfunction "26_26") (pintype "passive"))
    )
    (net (code "81") (name "unconnected-(P1-Pad27)") (class "Default")
      (node (ref "P1") (pin "27") (pinfunction "27_27") (pintype "passive"))
    )
    (net (code "82") (name "unconnected-(P1-Pad28)") (class "Default")
      (node (ref "P1") (pin "28") (pinfunction "28_28") (pintype "passive"))
    )
    (net (code "83") (name "unconnected-(P1-Pad32)") (class "Default")
      (node (ref "P1") (pin "32") (pinfunction "32_32") (pintype "passive"))
    )
    (net (code "84") (name "unconnected-(P1-Pad35)") (class "Default")
      (node (ref "P1") (pin "35") (pinfunction "35_35") (pintype "passive"))
    )
    (net (code "85") (name "unconnected-(P1-Pad37)") (class "Default")
      (node (ref "P1") (pin "37") (pinfunction "37_37") (pintype "passive"))
    )
    (net (code "86") (name "unconnected-(P1-Pad38)") (class "Default")
      (node (ref "P1") (pin "38") (pinfunction "38_38") (pintype "passive"))
    )
    (net (code "87") (name "unconnected-(P1-Pad40)") (class "Default")
      (node (ref "P1") (pin "40") (pinfunction "40_40") (pintype "passive"))
    )
  )
)
